# 05_MCU.net
KiCad netlist of a schematic drawn in Altium Designer
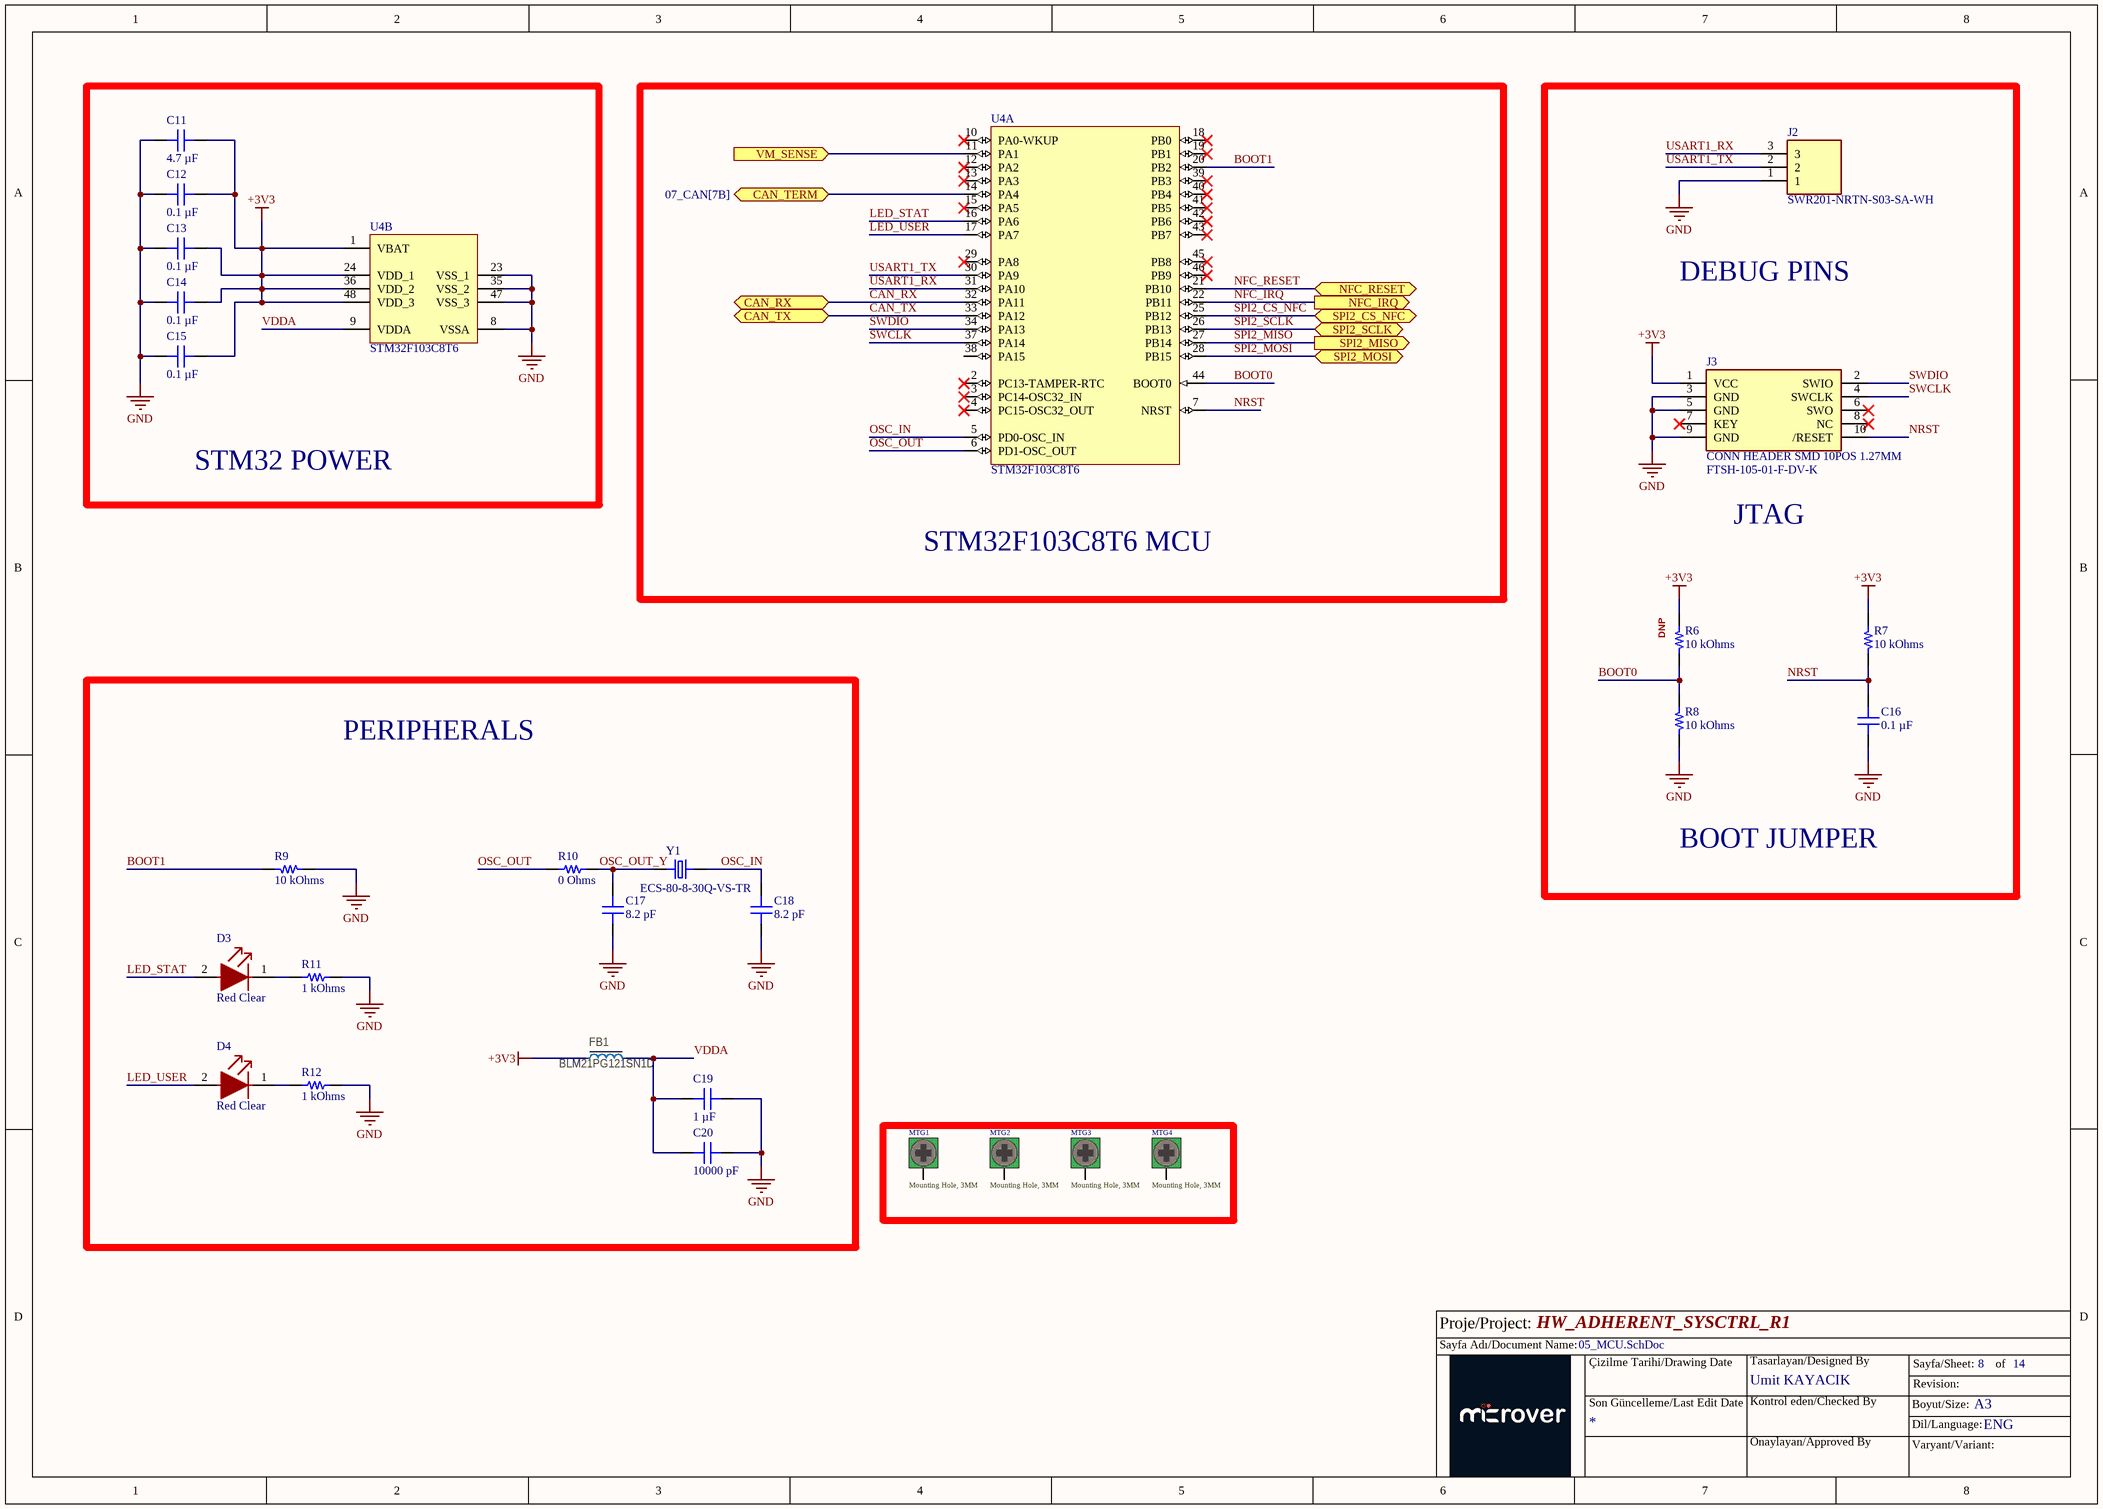
[diagram p0: 05_MCU.SchDoc]

(export (version "E")
  (design (tool "Eeschema 10.0.6"))
  (components
    (comp (ref "C11")
      (value "4.7 µF")
      (footprint "CAP 0805_2012")
      (description "CAP CER 4.7UF 50V X7R 0805")
      (fields
        (field (name "PART NUMBER") "GRM21BZ71H475KE15K")
        (field (name "CAPACITANCE") "4.7 µF")
        (field (name "MANUFACTURER") "Murata Electronics")
      )
      (libsource (lib "Celestial Altium Library - altium_library") (part "Capacitor"))
    )
    (comp (ref "C12")
      (value "GCM188R71H104KA57J")
      (footprint "CAP 0603_1608")
      (description "CAP CER 0.1UF 50V X7R 0603")
      (fields
        (field (name "CAPACITANCE") "0.1 µF")
        (field (name "MANUFACTURER") "Murata Electronics")
        (field (name "TOLERANCE") "±10%")
      )
      (libsource (lib "Celestial Altium Library - altium_library") (part "Capacitor"))
    )
    (comp (ref "C13")
      (value "GCM188R71H104KA57J")
      (footprint "CAP 0603_1608")
      (description "CAP CER 0.1UF 50V X7R 0603")
      (fields
        (field (name "CAPACITANCE") "0.1 µF")
        (field (name "MANUFACTURER") "Murata Electronics")
        (field (name "TOLERANCE") "±10%")
      )
      (libsource (lib "Celestial Altium Library - altium_library") (part "Capacitor"))
    )
    (comp (ref "C14")
      (value "GCM188R71H104KA57J")
      (footprint "CAP 0603_1608")
      (description "CAP CER 0.1UF 50V X7R 0603")
      (fields
        (field (name "CAPACITANCE") "0.1 µF")
        (field (name "MANUFACTURER") "Murata Electronics")
        (field (name "TOLERANCE") "±10%")
      )
      (libsource (lib "Celestial Altium Library - altium_library") (part "Capacitor"))
    )
    (comp (ref "C15")
      (value "GCM188R71H104KA57J")
      (footprint "CAP 0603_1608")
      (description "CAP CER 0.1UF 50V X7R 0603")
      (fields
        (field (name "CAPACITANCE") "0.1 µF")
        (field (name "MANUFACTURER") "Murata Electronics")
        (field (name "TOLERANCE") "±10%")
      )
      (libsource (lib "Celestial Altium Library - altium_library") (part "Capacitor"))
    )
    (comp (ref "C16")
      (value "GCM188R71H104KA57J")
      (footprint "CAP 0603_1608")
      (description "CAP CER 0.1UF 50V X7R 0603")
      (fields
        (field (name "CAPACITANCE") "0.1 µF")
        (field (name "MANUFACTURER") "Murata Electronics")
        (field (name "TOLERANCE") "±10%")
      )
      (libsource (lib "Celestial Altium Library - altium_library") (part "Capacitor"))
    )
    (comp (ref "C17")
      (value "8.2 pF")
      (footprint "CAP 0402_1005")
      (description "CAP0402 COG 8.2PF 5% 25V")
      (fields
        (field (name "PART NUMBER") "GMC04CG8R2J25NT")
        (field (name "CAPACITANCE") "8.2 pF")
        (field (name "MANUFACTURER") "Cal-Chip Electronics, Inc.")
      )
      (libsource (lib "Celestial Altium Library - altium_library") (part "Capacitor"))
    )
    (comp (ref "C18")
      (value "8.2 pF")
      (footprint "CAP 0402_1005")
      (description "CAP0402 COG 8.2PF 5% 25V")
      (fields
        (field (name "PART NUMBER") "GMC04CG8R2J25NT")
        (field (name "CAPACITANCE") "8.2 pF")
        (field (name "MANUFACTURER") "Cal-Chip Electronics, Inc.")
      )
      (libsource (lib "Celestial Altium Library - altium_library") (part "Capacitor"))
    )
    (comp (ref "C19")
      (value "1 µF")
      (footprint "CAP 0603_1608")
      (description "CAP0603 X7R 1UF 10% 25V")
      (fields
        (field (name "PART NUMBER") "GMC10X7R105K25NT")
        (field (name "CAPACITANCE") "1 µF")
        (field (name "MANUFACTURER") "Cal-Chip Electronics, Inc.")
      )
      (libsource (lib "Celestial Altium Library - altium_library") (part "Capacitor"))
    )
    (comp (ref "C20")
      (value "10000 pF")
      (footprint "CAP 0603_1608")
      (description "CAP CER 0603 10NF 16V X7R 10%")
      (fields
        (field (name "PART NUMBER") "C0603C103K4RECTU")
        (field (name "CAPACITANCE") "10000 pF")
        (field (name "MANUFACTURER") "KEMET")
      )
      (libsource (lib "Celestial Altium Library - altium_library") (part "Capacitor"))
    )
    (comp (ref "D3")
      (value "LED RED CLEAR SMD")
      (footprint "Lite-On_RED_0603")
      (description "Red 631nm LED Indication - Discrete 2V 0603 (1608 Metric)")
      (fields
        (field (name "MANUFACTURER") "Lite-On Inc.")
        (field (name "MANUFACTURER PART NUMBER") "LTST-C191KRKT")
        (field (name "COLOR") "Red Clear")
      )
      (libsource (lib "HW_ADHERENT_NFC_R1_L3") (part "LTST-C191KRKT_2"))
    )
    (comp (ref "D4")
      (value "LED RED CLEAR SMD")
      (footprint "Lite-On_RED_0603")
      (description "Red 631nm LED Indication - Discrete 2V 0603 (1608 Metric)")
      (fields
        (field (name "MANUFACTURER") "Lite-On Inc.")
        (field (name "MANUFACTURER PART NUMBER") "LTST-C191KRKT")
        (field (name "COLOR") "Red Clear")
      )
      (libsource (lib "HW_ADHERENT_NFC_R1_L3") (part "LTST-C191KRKT_2"))
    )
    (comp (ref "FB1")
      (value "BLM21PG121SN1D")
      (footprint "INDC2012X11L")
      (description "Ferrite Bead, 120 Ohm @ 100MHz, 500mA, 250 mOhm Max")
      (fields
        (field (name "PART NUMBER") "FB0402-120R@100M-500mA")
        (field (name "MANUFACTURER") "Murata")
        (field (name "AUTHOR") "rsk")
      )
      (libsource (lib "HW_PEINFO_CRANECTRL_KEY20_R1") (part "FB0402-120R@100M-500mA"))
    )
    (comp (ref "J2")
      (value "SWR201-NRTN-S03-SA-WH")
      (footprint "SHDR3W50P0X200_1X3_790X460X630P")
      (description "Connector")
      (libsource (lib "HW_PEINFO_CRANECTRL_KEY20_R1") (part "SWR201-NRTN-S03-SA-WH"))
    )
    (comp (ref "J3")
      (value "CONN HEADER SMD 10POS 1.27MM")
      (footprint "Samtec_0_MFG")
      (description "Connector Header Surface Mount 10 position 0.050\" (1.27mm)")
      (fields (field (name "MANUFACTURER PART NUMBER") "FTSH-105-01-F-DV-K"))
      (libsource (lib "HW_PEINFO_RF_RECEIVER_R1") (part "FTSH-105-01-F-DV-K"))
    )
    (comp (ref "MTG1")
      (value "Mounting Hole, 3MM")
      (footprint "MTG-PTH-3MM")
      (libsource (lib "HW_ADHERENT_SYSCTRL_R1_L2") (part "MTG3MM"))
    )
    (comp (ref "MTG2")
      (value "Mounting Hole, 3MM")
      (footprint "MTG-PTH-3MM")
      (libsource (lib "HW_ADHERENT_SYSCTRL_R1_L2") (part "MTG3MM"))
    )
    (comp (ref "MTG3")
      (value "Mounting Hole, 3MM")
      (footprint "MTG-PTH-3MM")
      (libsource (lib "HW_ADHERENT_SYSCTRL_R1_L2") (part "MTG3MM"))
    )
    (comp (ref "MTG4")
      (value "Mounting Hole, 3MM")
      (footprint "MTG-PTH-3MM")
      (libsource (lib "HW_ADHERENT_SYSCTRL_R1_L2") (part "MTG3MM"))
    )
    (comp (ref "R6")
      (value "10 kOhms")
      (footprint "RES 0402_1005")
      (description "RES 10K OHM 1% 1/16W 0402")
      (fields
        (field (name "PART NUMBER") "RMCF0402FT10K0")
        (field (name "MANUFACTURER") "Stackpole Electronics Inc")
      )
      (libsource (lib "Celestial Altium Library - altium_library") (part "Resistor"))
    )
    (comp (ref "R7")
      (value "10 kOhms")
      (footprint "RES 0402_1005")
      (description "RES 10K OHM 1% 1/16W 0402")
      (fields
        (field (name "PART NUMBER") "RMCF0402FT10K0")
        (field (name "MANUFACTURER") "Stackpole Electronics Inc")
      )
      (libsource (lib "Celestial Altium Library - altium_library") (part "Resistor"))
    )
    (comp (ref "R8")
      (value "10 kOhms")
      (footprint "RES 0402_1005")
      (description "RES 10K OHM 1% 1/16W 0402")
      (fields
        (field (name "PART NUMBER") "RMCF0402FT10K0")
        (field (name "MANUFACTURER") "Stackpole Electronics Inc")
      )
      (libsource (lib "Celestial Altium Library - altium_library") (part "Resistor"))
    )
    (comp (ref "R9")
      (value "10 kOhms")
      (footprint "RES 0402_1005")
      (description "RES 10K OHM 1% 1/16W 0402")
      (fields
        (field (name "PART NUMBER") "RMCF0402FT10K0")
        (field (name "MANUFACTURER") "Stackpole Electronics Inc")
      )
      (libsource (lib "Celestial Altium Library - altium_library") (part "Resistor"))
    )
    (comp (ref "R10")
      (value "0 Ohms")
      (footprint "RES 0402_1005")
      (description "RES 0 OHM JUMPER 1/16W 0402")
      (fields
        (field (name "PART NUMBER") "RMCF0402ZT0R00")
        (field (name "MANUFACTURER") "Stackpole Electronics Inc")
      )
      (libsource (lib "Celestial Altium Library - altium_library") (part "Resistor"))
    )
    (comp (ref "R11")
      (value "1 kOhms")
      (footprint "RES 0402_1005")
      (description "RES 1K OHM 1% 1/16W 0402")
      (fields
        (field (name "PART NUMBER") "RMCF0402FT1K00")
        (field (name "MANUFACTURER") "Stackpole Electronics Inc")
      )
      (libsource (lib "Celestial Altium Library - altium_library") (part "Resistor"))
    )
    (comp (ref "R12")
      (value "1 kOhms")
      (footprint "RES 0402_1005")
      (description "RES 1K OHM 1% 1/16W 0402")
      (fields
        (field (name "PART NUMBER") "RMCF0402FT1K00")
        (field (name "MANUFACTURER") "Stackpole Electronics Inc")
      )
      (libsource (lib "Celestial Altium Library - altium_library") (part "Resistor"))
    )
    (comp (ref "U4")
      (value "STM32F103C8T6")
      (footprint "LQFP48_STM")
      (fields (field (name "LCSC PART NUMBER") "C8734"))
      (libsource (lib "HW_PEINFO_RF_RECEIVER_R1") (part "STM32F103C8T6"))
    )
    (comp (ref "Y1")
      (value "ECS-80-8-30Q-VS-TR")
      (footprint "XTAL_ECS-80-8-30Q-VS-TR")
      (description "8 MHz Â±30ppm Crystal 8pF 100 Ohms 2-SMD, No Lead")
      (fields (field (name "MF") "ECS Inc."))
      (libsource (lib "HW_PEINFO_CRANECTRL_KEY20_R1") (part "ECS-80-8-30Q-VS-TR"))
    )
  )
  (nets
    (net (code "1") (name "+3V3") (class "Default")
      (node (ref "C11") (pin "2") (pinfunction "2_2") (pintype "passive"))
      (node (ref "C12") (pin "1") (pinfunction "1_1") (pintype "passive"))
      (node (ref "C13") (pin "1") (pinfunction "1_1") (pintype "passive"))
      (node (ref "C14") (pin "1") (pinfunction "1_1") (pintype "passive"))
      (node (ref "C15") (pin "1") (pinfunction "1_1") (pintype "passive"))
      (node (ref "FB1") (pin "1") (pinfunction "1_1") (pintype "passive"))
      (node (ref "J3") (pin "1") (pinfunction "VCC_1") (pintype "passive"))
      (node (ref "R6") (pin "1") (pinfunction "1_1") (pintype "passive"))
      (node (ref "R7") (pin "1") (pinfunction "1_1") (pintype "passive"))
      (node (ref "U4") (pin "1") (pinfunction "VBAT_1") (pintype "power_in"))
      (node (ref "U4") (pin "24") (pinfunction "VDD_1_24") (pintype "power_in"))
      (node (ref "U4") (pin "36") (pinfunction "VDD_2_36") (pintype "power_in"))
      (node (ref "U4") (pin "48") (pinfunction "VDD_3_48") (pintype "power_in"))
    )
    (net (code "2") (name "/BOOT0") (class "Default")
      (node (ref "R6") (pin "2") (pinfunction "2_2") (pintype "passive"))
      (node (ref "R8") (pin "1") (pinfunction "1_1") (pintype "passive"))
      (node (ref "U4") (pin "44") (pinfunction "BOOT0_44") (pintype "input"))
    )
    (net (code "3") (name "/BOOT1") (class "Default")
      (node (ref "R9") (pin "2") (pinfunction "2_2") (pintype "passive"))
      (node (ref "U4") (pin "20") (pinfunction "PB2_20") (pintype "bidirectional"))
    )
    (net (code "4") (name "/CAN_RX") (class "Default")
      (node (ref "U4") (pin "32") (pinfunction "PA11_32") (pintype "bidirectional"))
    )
    (net (code "5") (name "/CAN_TERM") (class "Default")
      (node (ref "U4") (pin "14") (pinfunction "PA4_14") (pintype "bidirectional"))
    )
    (net (code "6") (name "/CAN_TX") (class "Default")
      (node (ref "U4") (pin "33") (pinfunction "PA12_33") (pintype "bidirectional"))
    )
    (net (code "7") (name "/LED_STAT") (class "Default")
      (node (ref "D3") (pin "2") (pinfunction "A_2") (pintype "passive"))
      (node (ref "U4") (pin "16") (pinfunction "PA6_16") (pintype "bidirectional"))
    )
    (net (code "8") (name "/LED_USER") (class "Default")
      (node (ref "D4") (pin "2") (pinfunction "A_2") (pintype "passive"))
      (node (ref "U4") (pin "17") (pinfunction "PA7_17") (pintype "bidirectional"))
    )
    (net (code "9") (name "/NFC_IRQ") (class "Default")
      (node (ref "U4") (pin "22") (pinfunction "PB11_22") (pintype "bidirectional"))
    )
    (net (code "10") (name "/NFC_RESET") (class "Default")
      (node (ref "U4") (pin "21") (pinfunction "PB10_21") (pintype "bidirectional"))
    )
    (net (code "11") (name "/NRST") (class "Default")
      (node (ref "C16") (pin "1") (pinfunction "1_1") (pintype "passive"))
      (node (ref "J3") (pin "10") (pinfunction "/RESET_10") (pintype "passive"))
      (node (ref "R7") (pin "2") (pinfunction "2_2") (pintype "passive"))
      (node (ref "U4") (pin "7") (pinfunction "NRST_7") (pintype "bidirectional"))
    )
    (net (code "12") (name "/OSC_IN") (class "Default")
      (node (ref "C18") (pin "2") (pinfunction "2_2") (pintype "passive"))
      (node (ref "U4") (pin "5") (pinfunction "PD0-OSC_IN_5") (pintype "bidirectional"))
      (node (ref "Y1") (pin "2") (pinfunction "OUT/IN_2") (pintype "passive"))
    )
    (net (code "13") (name "/OSC_OUT") (class "Default")
      (node (ref "R10") (pin "1") (pinfunction "1_1") (pintype "passive"))
      (node (ref "U4") (pin "6") (pinfunction "PD1-OSC_OUT_6") (pintype "bidirectional"))
    )
    (net (code "14") (name "/OSC_OUT_Y") (class "Default")
      (node (ref "C17") (pin "2") (pinfunction "2_2") (pintype "passive"))
      (node (ref "R10") (pin "2") (pinfunction "2_2") (pintype "passive"))
      (node (ref "Y1") (pin "1") (pinfunction "IN/OUT_1") (pintype "passive"))
    )
    (net (code "15") (name "/SPI2_CS_NFC") (class "Default")
      (node (ref "U4") (pin "25") (pinfunction "PB12_25") (pintype "bidirectional"))
    )
    (net (code "16") (name "/SPI2_MISO") (class "Default")
      (node (ref "U4") (pin "27") (pinfunction "PB14_27") (pintype "bidirectional"))
    )
    (net (code "17") (name "/SPI2_MOSI") (class "Default")
      (node (ref "U4") (pin "28") (pinfunction "PB15_28") (pintype "bidirectional"))
    )
    (net (code "18") (name "/SPI2_SCLK") (class "Default")
      (node (ref "U4") (pin "26") (pinfunction "PB13_26") (pintype "bidirectional"))
    )
    (net (code "19") (name "/SWCLK") (class "Default")
      (node (ref "J3") (pin "4") (pinfunction "SWCLK_4") (pintype "passive"))
      (node (ref "U4") (pin "37") (pinfunction "PA14_37") (pintype "bidirectional"))
    )
    (net (code "20") (name "/SWDIO") (class "Default")
      (node (ref "J3") (pin "2") (pinfunction "SWIO_2") (pintype "passive"))
      (node (ref "U4") (pin "34") (pinfunction "PA13_34") (pintype "bidirectional"))
    )
    (net (code "21") (name "/USART1_RX") (class "Default")
      (node (ref "J2") (pin "3") (pinfunction "3_3") (pintype "passive"))
      (node (ref "U4") (pin "31") (pinfunction "PA10_31") (pintype "bidirectional"))
    )
    (net (code "22") (name "/USART1_TX") (class "Default")
      (node (ref "J2") (pin "2") (pinfunction "2_2") (pintype "passive"))
      (node (ref "U4") (pin "30") (pinfunction "PA9_30") (pintype "bidirectional"))
    )
    (net (code "23") (name "/VDDA") (class "Default")
      (node (ref "C19") (pin "1") (pinfunction "1_1") (pintype "passive"))
      (node (ref "C20") (pin "1") (pinfunction "1_1") (pintype "passive"))
      (node (ref "FB1") (pin "2") (pinfunction "2_2") (pintype "passive"))
      (node (ref "U4") (pin "9") (pinfunction "VDDA_9") (pintype "power_in"))
    )
    (net (code "24") (name "/VM_SENSE") (class "Default")
      (node (ref "U4") (pin "11") (pinfunction "PA1_11") (pintype "bidirectional"))
    )
    (net (code "25") (name "GND") (class "Default")
      (node (ref "C11") (pin "1") (pinfunction "1_1") (pintype "passive"))
      (node (ref "C12") (pin "2") (pinfunction "2_2") (pintype "passive"))
      (node (ref "C13") (pin "2") (pinfunction "2_2") (pintype "passive"))
      (node (ref "C14") (pin "2") (pinfunction "2_2") (pintype "passive"))
      (node (ref "C15") (pin "2") (pinfunction "2_2") (pintype "passive"))
      (node (ref "C16") (pin "2") (pinfunction "2_2") (pintype "passive"))
      (node (ref "C17") (pin "1") (pinfunction "1_1") (pintype "passive"))
      (node (ref "C18") (pin "1") (pinfunction "1_1") (pintype "passive"))
      (node (ref "C19") (pin "2") (pinfunction "2_2") (pintype "passive"))
      (node (ref "C20") (pin "2") (pinfunction "2_2") (pintype "passive"))
      (node (ref "J2") (pin "1") (pinfunction "1_1") (pintype "passive"))
      (node (ref "J3") (pin "3") (pinfunction "GND_3") (pintype "passive"))
      (node (ref "J3") (pin "5") (pinfunction "GND_5") (pintype "passive"))
      (node (ref "J3") (pin "9") (pinfunction "GND_9") (pintype "passive"))
      (node (ref "R11") (pin "2") (pinfunction "2_2") (pintype "passive"))
      (node (ref "R12") (pin "2") (pinfunction "2_2") (pintype "passive"))
      (node (ref "R8") (pin "2") (pinfunction "2_2") (pintype "passive"))
      (node (ref "R9") (pin "1") (pinfunction "1_1") (pintype "passive"))
      (node (ref "U4") (pin "23") (pinfunction "VSS_1_23") (pintype "passive"))
      (node (ref "U4") (pin "35") (pinfunction "VSS_2_35") (pintype "passive"))
      (node (ref "U4") (pin "47") (pinfunction "VSS_3_47") (pintype "passive"))
      (node (ref "U4") (pin "8") (pinfunction "VSSA_8") (pintype "passive"))
    )
    (net (code "26") (name "Net-(D3-C)") (class "Default")
      (node (ref "D3") (pin "1") (pinfunction "C_1") (pintype "passive"))
      (node (ref "R11") (pin "1") (pinfunction "1_1") (pintype "passive"))
    )
    (net (code "27") (name "Net-(D4-C)") (class "Default")
      (node (ref "D4") (pin "1") (pinfunction "C_1") (pintype "passive"))
      (node (ref "R12") (pin "1") (pinfunction "1_1") (pintype "passive"))
    )
    (net (code "28") (name "unconnected-(J3-KEY-Pad7)") (class "Default")
      (node (ref "J3") (pin "7") (pinfunction "KEY_7") (pintype "passive+no_connect"))
    )
    (net (code "29") (name "unconnected-(J3-NC-Pad8)") (class "Default")
      (node (ref "J3") (pin "8") (pinfunction "NC_8") (pintype "passive+no_connect"))
    )
    (net (code "30") (name "unconnected-(J3-SWO-Pad6)") (class "Default")
      (node (ref "J3") (pin "6") (pinfunction "SWO_6") (pintype "passive+no_connect"))
    )
    (net (code "31") (name "unconnected-(MTG1-Pad0)") (class "Default")
      (node (ref "MTG1") (pin "0") (pinfunction "0_0") (pintype "passive"))
    )
    (net (code "32") (name "unconnected-(MTG2-Pad0)") (class "Default")
      (node (ref "MTG2") (pin "0") (pinfunction "0_0") (pintype "passive"))
    )
    (net (code "33") (name "unconnected-(MTG3-Pad0)") (class "Default")
      (node (ref "MTG3") (pin "0") (pinfunction "0_0") (pintype "passive"))
    )
    (net (code "34") (name "unconnected-(MTG4-Pad0)") (class "Default")
      (node (ref "MTG4") (pin "0") (pinfunction "0_0") (pintype "passive"))
    )
    (net (code "35") (name "unconnected-(U4A-PA0-WKUP-Pad10)") (class "Default")
      (node (ref "U4") (pin "10") (pinfunction "PA0-WKUP_10") (pintype "bidirectional+no_connect"))
    )
    (net (code "36") (name "unconnected-(U4A-PA2-Pad12)") (class "Default")
      (node (ref "U4") (pin "12") (pinfunction "PA2_12") (pintype "bidirectional+no_connect"))
    )
    (net (code "37") (name "unconnected-(U4A-PA3-Pad13)") (class "Default")
      (node (ref "U4") (pin "13") (pinfunction "PA3_13") (pintype "bidirectional+no_connect"))
    )
    (net (code "38") (name "unconnected-(U4A-PA5-Pad15)") (class "Default")
      (node (ref "U4") (pin "15") (pinfunction "PA5_15") (pintype "bidirectional+no_connect"))
    )
    (net (code "39") (name "unconnected-(U4A-PA8-Pad29)") (class "Default")
      (node (ref "U4") (pin "29") (pinfunction "PA8_29") (pintype "bidirectional+no_connect"))
    )
    (net (code "40") (name "unconnected-(U4A-PA15-Pad38)") (class "Default")
      (node (ref "U4") (pin "38") (pinfunction "PA15_38") (pintype "bidirectional"))
    )
    (net (code "41") (name "unconnected-(U4A-PB0-Pad18)") (class "Default")
      (node (ref "U4") (pin "18") (pinfunction "PB0_18") (pintype "bidirectional+no_connect"))
    )
    (net (code "42") (name "unconnected-(U4A-PB1-Pad19)") (class "Default")
      (node (ref "U4") (pin "19") (pinfunction "PB1_19") (pintype "bidirectional+no_connect"))
    )
    (net (code "43") (name "unconnected-(U4A-PB3-Pad39)") (class "Default")
      (node (ref "U4") (pin "39") (pinfunction "PB3_39") (pintype "bidirectional+no_connect"))
    )
    (net (code "44") (name "unconnected-(U4A-PB4-Pad40)") (class "Default")
      (node (ref "U4") (pin "40") (pinfunction "PB4_40") (pintype "bidirectional+no_connect"))
    )
    (net (code "45") (name "unconnected-(U4A-PB5-Pad41)") (class "Default")
      (node (ref "U4") (pin "41") (pinfunction "PB5_41") (pintype "bidirectional+no_connect"))
    )
    (net (code "46") (name "unconnected-(U4A-PB6-Pad42)") (class "Default")
      (node (ref "U4") (pin "42") (pinfunction "PB6_42") (pintype "bidirectional+no_connect"))
    )
    (net (code "47") (name "unconnected-(U4A-PB7-Pad43)") (class "Default")
      (node (ref "U4") (pin "43") (pinfunction "PB7_43") (pintype "bidirectional+no_connect"))
    )
    (net (code "48") (name "unconnected-(U4A-PB8-Pad45)") (class "Default")
      (node (ref "U4") (pin "45") (pinfunction "PB8_45") (pintype "bidirectional+no_connect"))
    )
    (net (code "49") (name "unconnected-(U4A-PB9-Pad46)") (class "Default")
      (node (ref "U4") (pin "46") (pinfunction "PB9_46") (pintype "bidirectional+no_connect"))
    )
    (net (code "50") (name "unconnected-(U4A-PC13-TAMPER-RTC-Pad2)") (class "Default")
      (node (ref "U4") (pin "2") (pinfunction "PC13-TAMPER-RTC_2") (pintype "bidirectional+no_connect"))
    )
    (net (code "51") (name "unconnected-(U4A-PC14-OSC32_IN-Pad3)") (class "Default")
      (node (ref "U4") (pin "3") (pinfunction "PC14-OSC32_IN_3") (pintype "bidirectional+no_connect"))
    )
    (net (code "52") (name "unconnected-(U4A-PC15-OSC32_OUT-Pad4)") (class "Default")
      (node (ref "U4") (pin "4") (pinfunction "PC15-OSC32_OUT_4") (pintype "bidirectional+no_connect"))
    )
  )
)
